# ProDocument_frontend_2024-01-22.net
KiCad netlist of a schematic drawn in EasyEDA Pro
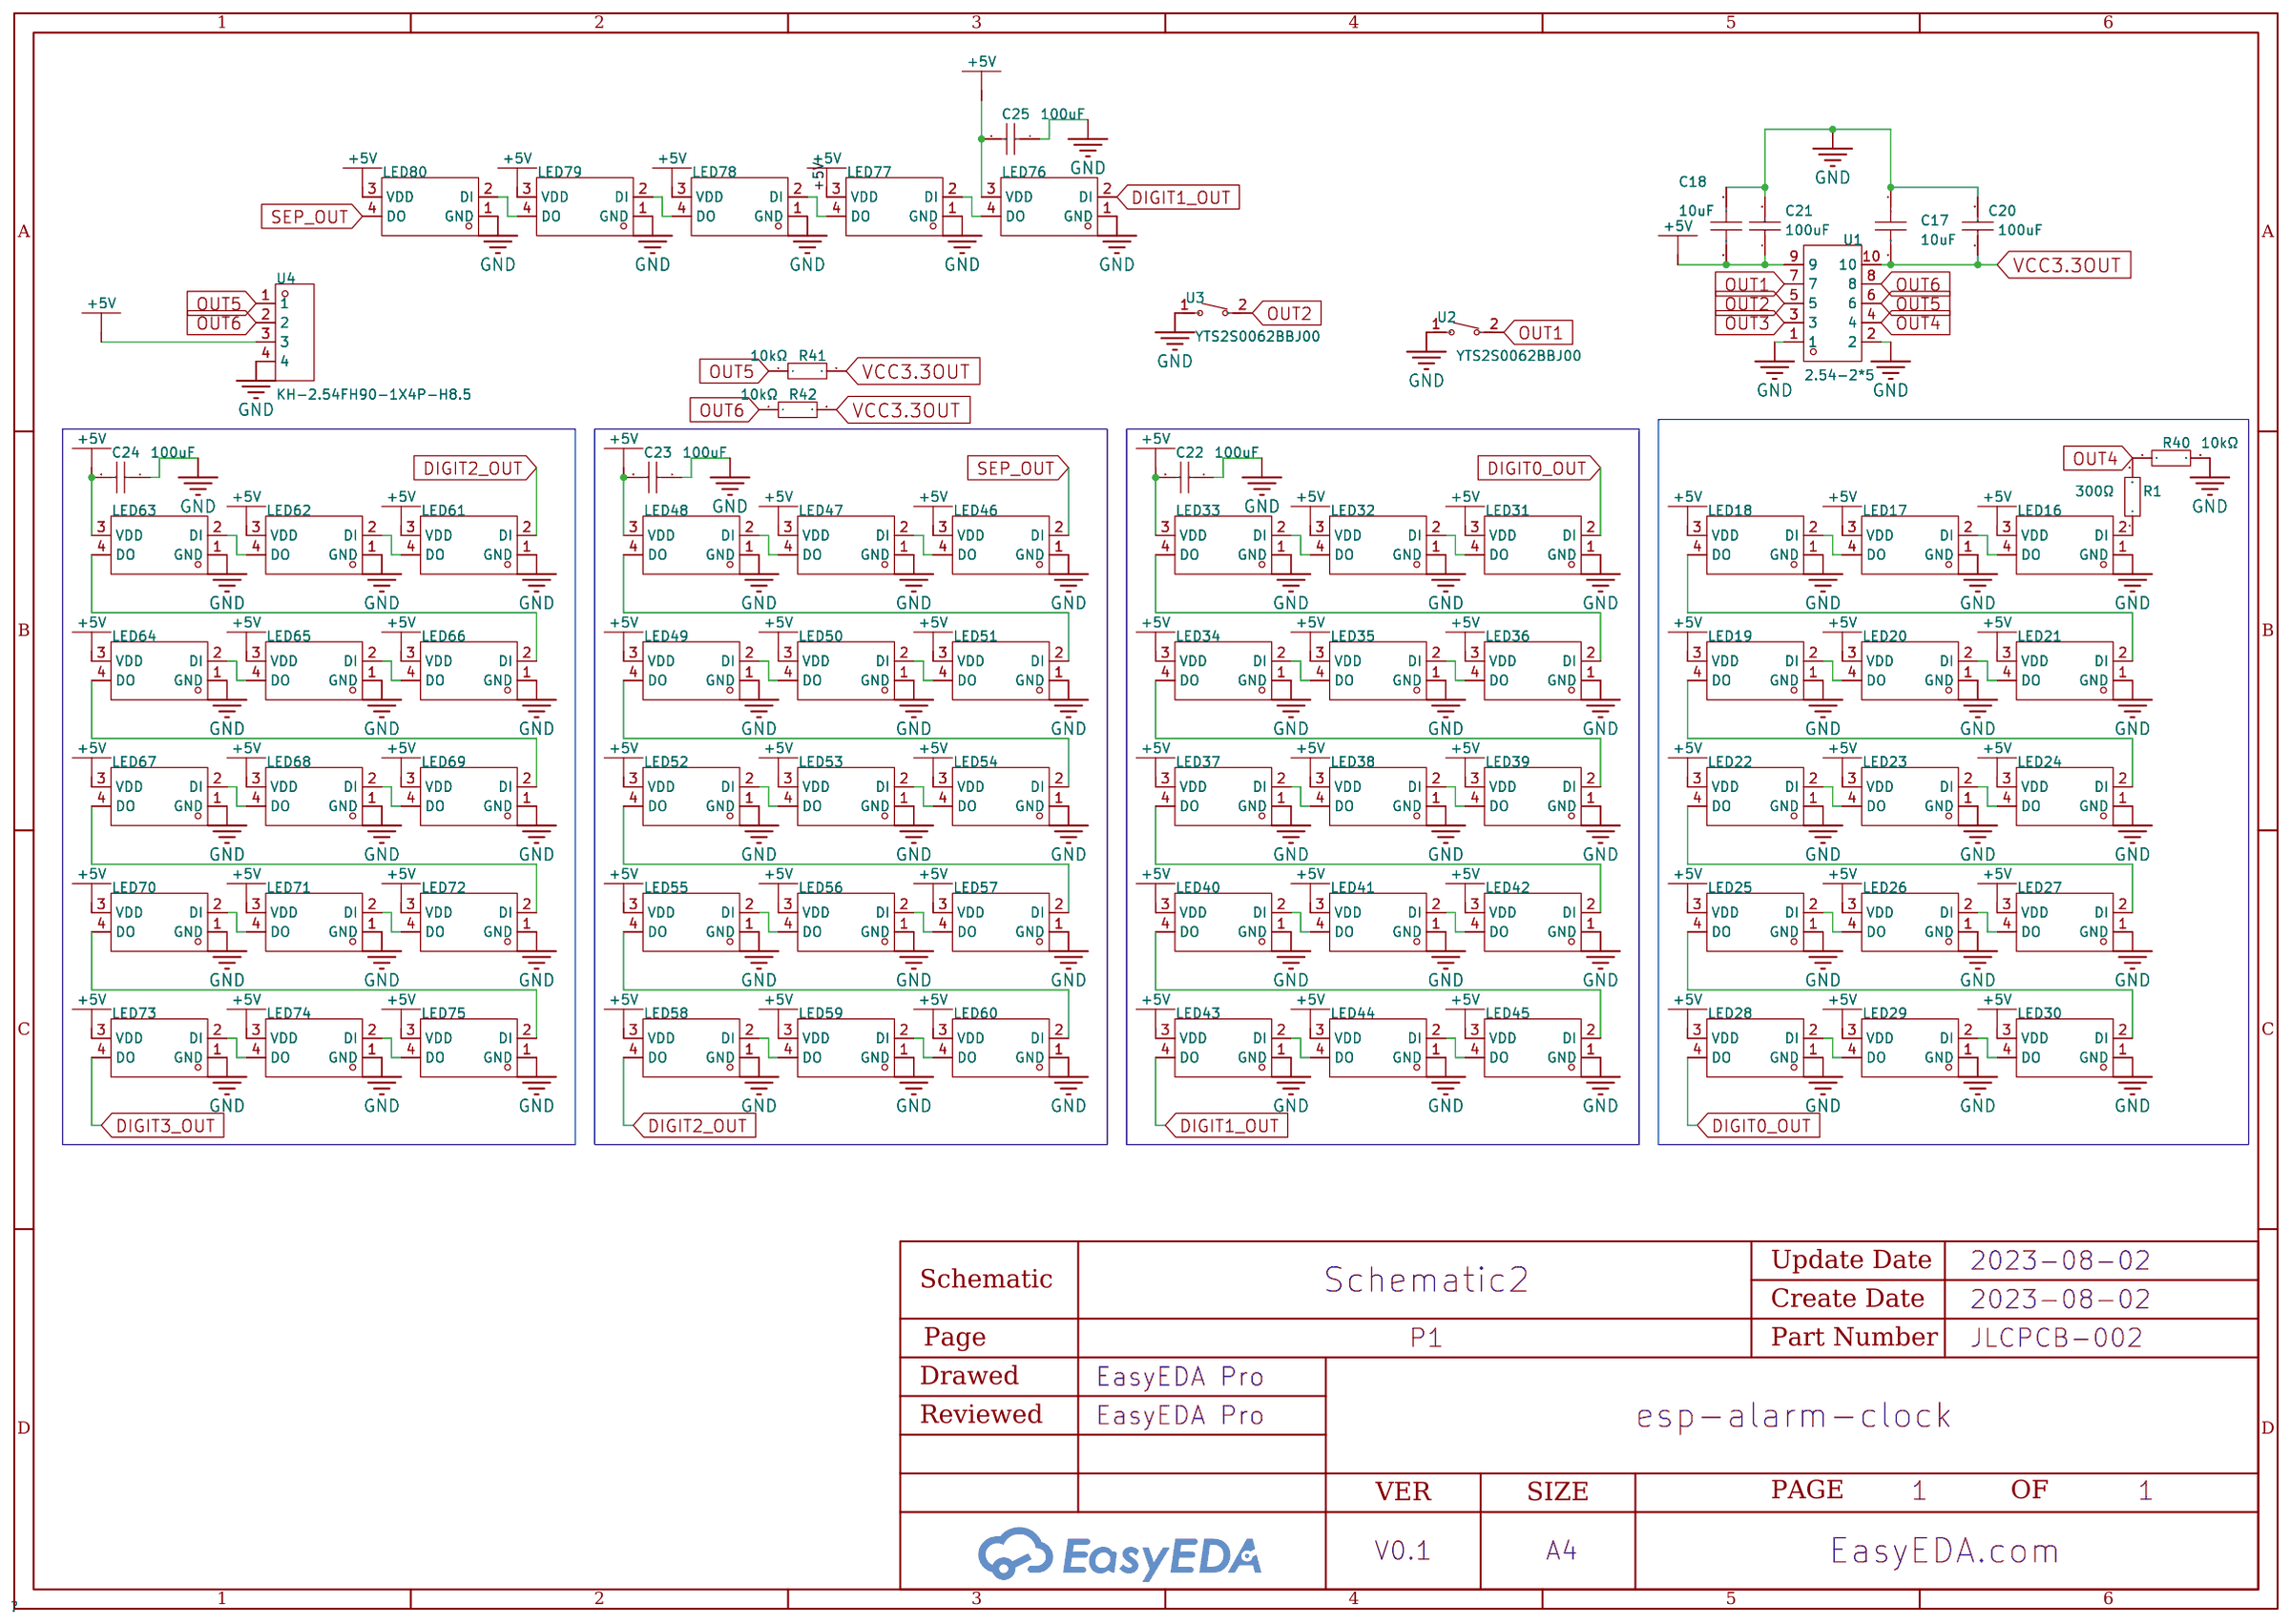
[diagram p0: schematic sheet]

(export (version "E")
  (design (tool "Eeschema 10.0.6"))
  (components
    (comp (ref "C17")
      (value "10uF")
      (footprint "easyedapro:C0603")
      (fields
        (field (name "Manufacturer Part") "TCC0603X5R106M6R3CT")
        (field (name "Manufacturer") "CCTC(三环)")
      )
      (libsource (lib "easyedapro") (part "TCC0603X5R106M6R3CT"))
    )
    (comp (ref "C18")
      (value "10uF")
      (footprint "easyedapro:C0603")
      (fields
        (field (name "Manufacturer Part") "TCC0603X5R106M6R3CT")
        (field (name "Manufacturer") "CCTC(三环)")
      )
      (libsource (lib "easyedapro") (part "TCC0603X5R106M6R3CT"))
    )
    (comp (ref "C20")
      (value "100uF")
      (footprint "easyedapro:C1206")
      (fields
        (field (name "Manufacturer Part") "CL31A107MQHNNNE")
        (field (name "Manufacturer") "SAMSUNG(三星)")
      )
      (libsource (lib "easyedapro") (part "CL31A107MQHNNNE"))
    )
    (comp (ref "C21")
      (value "100uF")
      (footprint "easyedapro:C1206")
      (fields
        (field (name "Manufacturer Part") "CL31A107MQHNNNE")
        (field (name "Manufacturer") "SAMSUNG(三星)")
      )
      (libsource (lib "easyedapro") (part "CL31A107MQHNNNE"))
    )
    (comp (ref "C22")
      (value "100uF")
      (footprint "easyedapro:C1206")
      (fields
        (field (name "Manufacturer Part") "CL31A107MQHNNNE")
        (field (name "Manufacturer") "SAMSUNG(三星)")
      )
      (libsource (lib "easyedapro") (part "CL31A107MQHNNNE"))
    )
    (comp (ref "C23")
      (value "100uF")
      (footprint "easyedapro:C1206")
      (fields
        (field (name "Manufacturer Part") "CL31A107MQHNNNE")
        (field (name "Manufacturer") "SAMSUNG(三星)")
      )
      (libsource (lib "easyedapro") (part "CL31A107MQHNNNE"))
    )
    (comp (ref "C24")
      (value "100uF")
      (footprint "easyedapro:C1206")
      (fields
        (field (name "Manufacturer Part") "CL31A107MQHNNNE")
        (field (name "Manufacturer") "SAMSUNG(三星)")
      )
      (libsource (lib "easyedapro") (part "CL31A107MQHNNNE"))
    )
    (comp (ref "C25")
      (value "100uF")
      (footprint "easyedapro:C1206")
      (fields
        (field (name "Manufacturer Part") "CL31A107MQHNNNE")
        (field (name "Manufacturer") "SAMSUNG(三星)")
      )
      (libsource (lib "easyedapro") (part "CL31A107MQHNNNE"))
    )
    (comp (ref "LED16")
      (value "XL-3528RGBW-WS2812B")
      (footprint "easyedapro:LED-SMD_4P-L3.5-W2.8-BR-1")
      (fields (field (name "Manufacturer") "XINGLIGHT(成兴光)"))
      (libsource (lib "easyedapro") (part "XL-3528RGBW-WS2812B"))
    )
    (comp (ref "LED17")
      (value "XL-3528RGBW-WS2812B")
      (footprint "easyedapro:LED-SMD_4P-L3.5-W2.8-BR-1")
      (fields (field (name "Manufacturer") "XINGLIGHT(成兴光)"))
      (libsource (lib "easyedapro") (part "XL-3528RGBW-WS2812B"))
    )
    (comp (ref "LED18")
      (value "XL-3528RGBW-WS2812B")
      (footprint "easyedapro:LED-SMD_4P-L3.5-W2.8-BR-1")
      (fields (field (name "Manufacturer") "XINGLIGHT(成兴光)"))
      (libsource (lib "easyedapro") (part "XL-3528RGBW-WS2812B"))
    )
    (comp (ref "LED19")
      (value "XL-3528RGBW-WS2812B")
      (footprint "easyedapro:LED-SMD_4P-L3.5-W2.8-BR-1")
      (fields (field (name "Manufacturer") "XINGLIGHT(成兴光)"))
      (libsource (lib "easyedapro") (part "XL-3528RGBW-WS2812B"))
    )
    (comp (ref "LED20")
      (value "XL-3528RGBW-WS2812B")
      (footprint "easyedapro:LED-SMD_4P-L3.5-W2.8-BR-1")
      (fields (field (name "Manufacturer") "XINGLIGHT(成兴光)"))
      (libsource (lib "easyedapro") (part "XL-3528RGBW-WS2812B"))
    )
    (comp (ref "LED21")
      (value "XL-3528RGBW-WS2812B")
      (footprint "easyedapro:LED-SMD_4P-L3.5-W2.8-BR-1")
      (fields (field (name "Manufacturer") "XINGLIGHT(成兴光)"))
      (libsource (lib "easyedapro") (part "XL-3528RGBW-WS2812B"))
    )
    (comp (ref "LED22")
      (value "XL-3528RGBW-WS2812B")
      (footprint "easyedapro:LED-SMD_4P-L3.5-W2.8-BR-1")
      (fields (field (name "Manufacturer") "XINGLIGHT(成兴光)"))
      (libsource (lib "easyedapro") (part "XL-3528RGBW-WS2812B"))
    )
    (comp (ref "LED23")
      (value "XL-3528RGBW-WS2812B")
      (footprint "easyedapro:LED-SMD_4P-L3.5-W2.8-BR-1")
      (fields (field (name "Manufacturer") "XINGLIGHT(成兴光)"))
      (libsource (lib "easyedapro") (part "XL-3528RGBW-WS2812B"))
    )
    (comp (ref "LED24")
      (value "XL-3528RGBW-WS2812B")
      (footprint "easyedapro:LED-SMD_4P-L3.5-W2.8-BR-1")
      (fields (field (name "Manufacturer") "XINGLIGHT(成兴光)"))
      (libsource (lib "easyedapro") (part "XL-3528RGBW-WS2812B"))
    )
    (comp (ref "LED25")
      (value "XL-3528RGBW-WS2812B")
      (footprint "easyedapro:LED-SMD_4P-L3.5-W2.8-BR-1")
      (fields (field (name "Manufacturer") "XINGLIGHT(成兴光)"))
      (libsource (lib "easyedapro") (part "XL-3528RGBW-WS2812B"))
    )
    (comp (ref "LED26")
      (value "XL-3528RGBW-WS2812B")
      (footprint "easyedapro:LED-SMD_4P-L3.5-W2.8-BR-1")
      (fields (field (name "Manufacturer") "XINGLIGHT(成兴光)"))
      (libsource (lib "easyedapro") (part "XL-3528RGBW-WS2812B"))
    )
    (comp (ref "LED27")
      (value "XL-3528RGBW-WS2812B")
      (footprint "easyedapro:LED-SMD_4P-L3.5-W2.8-BR-1")
      (fields (field (name "Manufacturer") "XINGLIGHT(成兴光)"))
      (libsource (lib "easyedapro") (part "XL-3528RGBW-WS2812B"))
    )
    (comp (ref "LED28")
      (value "XL-3528RGBW-WS2812B")
      (footprint "easyedapro:LED-SMD_4P-L3.5-W2.8-BR-1")
      (fields (field (name "Manufacturer") "XINGLIGHT(成兴光)"))
      (libsource (lib "easyedapro") (part "XL-3528RGBW-WS2812B"))
    )
    (comp (ref "LED29")
      (value "XL-3528RGBW-WS2812B")
      (footprint "easyedapro:LED-SMD_4P-L3.5-W2.8-BR-1")
      (fields (field (name "Manufacturer") "XINGLIGHT(成兴光)"))
      (libsource (lib "easyedapro") (part "XL-3528RGBW-WS2812B"))
    )
    (comp (ref "LED30")
      (value "XL-3528RGBW-WS2812B")
      (footprint "easyedapro:LED-SMD_4P-L3.5-W2.8-BR-1")
      (fields (field (name "Manufacturer") "XINGLIGHT(成兴光)"))
      (libsource (lib "easyedapro") (part "XL-3528RGBW-WS2812B"))
    )
    (comp (ref "LED31")
      (value "XL-3528RGBW-WS2812B")
      (footprint "easyedapro:LED-SMD_4P-L3.5-W2.8-BR-1")
      (fields (field (name "Manufacturer") "XINGLIGHT(成兴光)"))
      (libsource (lib "easyedapro") (part "XL-3528RGBW-WS2812B"))
    )
    (comp (ref "LED32")
      (value "XL-3528RGBW-WS2812B")
      (footprint "easyedapro:LED-SMD_4P-L3.5-W2.8-BR-1")
      (fields (field (name "Manufacturer") "XINGLIGHT(成兴光)"))
      (libsource (lib "easyedapro") (part "XL-3528RGBW-WS2812B"))
    )
    (comp (ref "LED33")
      (value "XL-3528RGBW-WS2812B")
      (footprint "easyedapro:LED-SMD_4P-L3.5-W2.8-BR-1")
      (fields (field (name "Manufacturer") "XINGLIGHT(成兴光)"))
      (libsource (lib "easyedapro") (part "XL-3528RGBW-WS2812B"))
    )
    (comp (ref "LED34")
      (value "XL-3528RGBW-WS2812B")
      (footprint "easyedapro:LED-SMD_4P-L3.5-W2.8-BR-1")
      (fields (field (name "Manufacturer") "XINGLIGHT(成兴光)"))
      (libsource (lib "easyedapro") (part "XL-3528RGBW-WS2812B"))
    )
    (comp (ref "LED35")
      (value "XL-3528RGBW-WS2812B")
      (footprint "easyedapro:LED-SMD_4P-L3.5-W2.8-BR-1")
      (fields (field (name "Manufacturer") "XINGLIGHT(成兴光)"))
      (libsource (lib "easyedapro") (part "XL-3528RGBW-WS2812B"))
    )
    (comp (ref "LED36")
      (value "XL-3528RGBW-WS2812B")
      (footprint "easyedapro:LED-SMD_4P-L3.5-W2.8-BR-1")
      (fields (field (name "Manufacturer") "XINGLIGHT(成兴光)"))
      (libsource (lib "easyedapro") (part "XL-3528RGBW-WS2812B"))
    )
    (comp (ref "LED37")
      (value "XL-3528RGBW-WS2812B")
      (footprint "easyedapro:LED-SMD_4P-L3.5-W2.8-BR-1")
      (fields (field (name "Manufacturer") "XINGLIGHT(成兴光)"))
      (libsource (lib "easyedapro") (part "XL-3528RGBW-WS2812B"))
    )
    (comp (ref "LED38")
      (value "XL-3528RGBW-WS2812B")
      (footprint "easyedapro:LED-SMD_4P-L3.5-W2.8-BR-1")
      (fields (field (name "Manufacturer") "XINGLIGHT(成兴光)"))
      (libsource (lib "easyedapro") (part "XL-3528RGBW-WS2812B"))
    )
    (comp (ref "LED39")
      (value "XL-3528RGBW-WS2812B")
      (footprint "easyedapro:LED-SMD_4P-L3.5-W2.8-BR-1")
      (fields (field (name "Manufacturer") "XINGLIGHT(成兴光)"))
      (libsource (lib "easyedapro") (part "XL-3528RGBW-WS2812B"))
    )
    (comp (ref "LED40")
      (value "XL-3528RGBW-WS2812B")
      (footprint "easyedapro:LED-SMD_4P-L3.5-W2.8-BR-1")
      (fields (field (name "Manufacturer") "XINGLIGHT(成兴光)"))
      (libsource (lib "easyedapro") (part "XL-3528RGBW-WS2812B"))
    )
    (comp (ref "LED41")
      (value "XL-3528RGBW-WS2812B")
      (footprint "easyedapro:LED-SMD_4P-L3.5-W2.8-BR-1")
      (fields (field (name "Manufacturer") "XINGLIGHT(成兴光)"))
      (libsource (lib "easyedapro") (part "XL-3528RGBW-WS2812B"))
    )
    (comp (ref "LED42")
      (value "XL-3528RGBW-WS2812B")
      (footprint "easyedapro:LED-SMD_4P-L3.5-W2.8-BR-1")
      (fields (field (name "Manufacturer") "XINGLIGHT(成兴光)"))
      (libsource (lib "easyedapro") (part "XL-3528RGBW-WS2812B"))
    )
    (comp (ref "LED43")
      (value "XL-3528RGBW-WS2812B")
      (footprint "easyedapro:LED-SMD_4P-L3.5-W2.8-BR-1")
      (fields (field (name "Manufacturer") "XINGLIGHT(成兴光)"))
      (libsource (lib "easyedapro") (part "XL-3528RGBW-WS2812B"))
    )
    (comp (ref "LED44")
      (value "XL-3528RGBW-WS2812B")
      (footprint "easyedapro:LED-SMD_4P-L3.5-W2.8-BR-1")
      (fields (field (name "Manufacturer") "XINGLIGHT(成兴光)"))
      (libsource (lib "easyedapro") (part "XL-3528RGBW-WS2812B"))
    )
    (comp (ref "LED45")
      (value "XL-3528RGBW-WS2812B")
      (footprint "easyedapro:LED-SMD_4P-L3.5-W2.8-BR-1")
      (fields (field (name "Manufacturer") "XINGLIGHT(成兴光)"))
      (libsource (lib "easyedapro") (part "XL-3528RGBW-WS2812B"))
    )
    (comp (ref "LED46")
      (value "XL-3528RGBW-WS2812B")
      (footprint "easyedapro:LED-SMD_4P-L3.5-W2.8-BR-1")
      (fields (field (name "Manufacturer") "XINGLIGHT(成兴光)"))
      (libsource (lib "easyedapro") (part "XL-3528RGBW-WS2812B"))
    )
    (comp (ref "LED47")
      (value "XL-3528RGBW-WS2812B")
      (footprint "easyedapro:LED-SMD_4P-L3.5-W2.8-BR-1")
      (fields (field (name "Manufacturer") "XINGLIGHT(成兴光)"))
      (libsource (lib "easyedapro") (part "XL-3528RGBW-WS2812B"))
    )
    (comp (ref "LED48")
      (value "XL-3528RGBW-WS2812B")
      (footprint "easyedapro:LED-SMD_4P-L3.5-W2.8-BR-1")
      (fields (field (name "Manufacturer") "XINGLIGHT(成兴光)"))
      (libsource (lib "easyedapro") (part "XL-3528RGBW-WS2812B"))
    )
    (comp (ref "LED49")
      (value "XL-3528RGBW-WS2812B")
      (footprint "easyedapro:LED-SMD_4P-L3.5-W2.8-BR-1")
      (fields (field (name "Manufacturer") "XINGLIGHT(成兴光)"))
      (libsource (lib "easyedapro") (part "XL-3528RGBW-WS2812B"))
    )
    (comp (ref "LED50")
      (value "XL-3528RGBW-WS2812B")
      (footprint "easyedapro:LED-SMD_4P-L3.5-W2.8-BR-1")
      (fields (field (name "Manufacturer") "XINGLIGHT(成兴光)"))
      (libsource (lib "easyedapro") (part "XL-3528RGBW-WS2812B"))
    )
    (comp (ref "LED51")
      (value "XL-3528RGBW-WS2812B")
      (footprint "easyedapro:LED-SMD_4P-L3.5-W2.8-BR-1")
      (fields (field (name "Manufacturer") "XINGLIGHT(成兴光)"))
      (libsource (lib "easyedapro") (part "XL-3528RGBW-WS2812B"))
    )
    (comp (ref "LED52")
      (value "XL-3528RGBW-WS2812B")
      (footprint "easyedapro:LED-SMD_4P-L3.5-W2.8-BR-1")
      (fields (field (name "Manufacturer") "XINGLIGHT(成兴光)"))
      (libsource (lib "easyedapro") (part "XL-3528RGBW-WS2812B"))
    )
    (comp (ref "LED53")
      (value "XL-3528RGBW-WS2812B")
      (footprint "easyedapro:LED-SMD_4P-L3.5-W2.8-BR-1")
      (fields (field (name "Manufacturer") "XINGLIGHT(成兴光)"))
      (libsource (lib "easyedapro") (part "XL-3528RGBW-WS2812B"))
    )
    (comp (ref "LED54")
      (value "XL-3528RGBW-WS2812B")
      (footprint "easyedapro:LED-SMD_4P-L3.5-W2.8-BR-1")
      (fields (field (name "Manufacturer") "XINGLIGHT(成兴光)"))
      (libsource (lib "easyedapro") (part "XL-3528RGBW-WS2812B"))
    )
    (comp (ref "LED55")
      (value "XL-3528RGBW-WS2812B")
      (footprint "easyedapro:LED-SMD_4P-L3.5-W2.8-BR-1")
      (fields (field (name "Manufacturer") "XINGLIGHT(成兴光)"))
      (libsource (lib "easyedapro") (part "XL-3528RGBW-WS2812B"))
    )
    (comp (ref "LED56")
      (value "XL-3528RGBW-WS2812B")
      (footprint "easyedapro:LED-SMD_4P-L3.5-W2.8-BR-1")
      (fields (field (name "Manufacturer") "XINGLIGHT(成兴光)"))
      (libsource (lib "easyedapro") (part "XL-3528RGBW-WS2812B"))
    )
    (comp (ref "LED57")
      (value "XL-3528RGBW-WS2812B")
      (footprint "easyedapro:LED-SMD_4P-L3.5-W2.8-BR-1")
      (fields (field (name "Manufacturer") "XINGLIGHT(成兴光)"))
      (libsource (lib "easyedapro") (part "XL-3528RGBW-WS2812B"))
    )
    (comp (ref "LED58")
      (value "XL-3528RGBW-WS2812B")
      (footprint "easyedapro:LED-SMD_4P-L3.5-W2.8-BR-1")
      (fields (field (name "Manufacturer") "XINGLIGHT(成兴光)"))
      (libsource (lib "easyedapro") (part "XL-3528RGBW-WS2812B"))
    )
    (comp (ref "LED59")
      (value "XL-3528RGBW-WS2812B")
      (footprint "easyedapro:LED-SMD_4P-L3.5-W2.8-BR-1")
      (fields (field (name "Manufacturer") "XINGLIGHT(成兴光)"))
      (libsource (lib "easyedapro") (part "XL-3528RGBW-WS2812B"))
    )
    (comp (ref "LED60")
      (value "XL-3528RGBW-WS2812B")
      (footprint "easyedapro:LED-SMD_4P-L3.5-W2.8-BR-1")
      (fields (field (name "Manufacturer") "XINGLIGHT(成兴光)"))
      (libsource (lib "easyedapro") (part "XL-3528RGBW-WS2812B"))
    )
    (comp (ref "LED61")
      (value "XL-3528RGBW-WS2812B")
      (footprint "easyedapro:LED-SMD_4P-L3.5-W2.8-BR-1")
      (fields (field (name "Manufacturer") "XINGLIGHT(成兴光)"))
      (libsource (lib "easyedapro") (part "XL-3528RGBW-WS2812B"))
    )
    (comp (ref "LED62")
      (value "XL-3528RGBW-WS2812B")
      (footprint "easyedapro:LED-SMD_4P-L3.5-W2.8-BR-1")
      (fields (field (name "Manufacturer") "XINGLIGHT(成兴光)"))
      (libsource (lib "easyedapro") (part "XL-3528RGBW-WS2812B"))
    )
    (comp (ref "LED63")
      (value "XL-3528RGBW-WS2812B")
      (footprint "easyedapro:LED-SMD_4P-L3.5-W2.8-BR-1")
      (fields (field (name "Manufacturer") "XINGLIGHT(成兴光)"))
      (libsource (lib "easyedapro") (part "XL-3528RGBW-WS2812B"))
    )
    (comp (ref "LED64")
      (value "XL-3528RGBW-WS2812B")
      (footprint "easyedapro:LED-SMD_4P-L3.5-W2.8-BR-1")
      (fields (field (name "Manufacturer") "XINGLIGHT(成兴光)"))
      (libsource (lib "easyedapro") (part "XL-3528RGBW-WS2812B"))
    )
    (comp (ref "LED65")
      (value "XL-3528RGBW-WS2812B")
      (footprint "easyedapro:LED-SMD_4P-L3.5-W2.8-BR-1")
      (fields (field (name "Manufacturer") "XINGLIGHT(成兴光)"))
      (libsource (lib "easyedapro") (part "XL-3528RGBW-WS2812B"))
    )
    (comp (ref "LED66")
      (value "XL-3528RGBW-WS2812B")
      (footprint "easyedapro:LED-SMD_4P-L3.5-W2.8-BR-1")
      (fields (field (name "Manufacturer") "XINGLIGHT(成兴光)"))
      (libsource (lib "easyedapro") (part "XL-3528RGBW-WS2812B"))
    )
    (comp (ref "LED67")
      (value "XL-3528RGBW-WS2812B")
      (footprint "easyedapro:LED-SMD_4P-L3.5-W2.8-BR-1")
      (fields (field (name "Manufacturer") "XINGLIGHT(成兴光)"))
      (libsource (lib "easyedapro") (part "XL-3528RGBW-WS2812B"))
    )
    (comp (ref "LED68")
      (value "XL-3528RGBW-WS2812B")
      (footprint "easyedapro:LED-SMD_4P-L3.5-W2.8-BR-1")
      (fields (field (name "Manufacturer") "XINGLIGHT(成兴光)"))
      (libsource (lib "easyedapro") (part "XL-3528RGBW-WS2812B"))
    )
    (comp (ref "LED69")
      (value "XL-3528RGBW-WS2812B")
      (footprint "easyedapro:LED-SMD_4P-L3.5-W2.8-BR-1")
      (fields (field (name "Manufacturer") "XINGLIGHT(成兴光)"))
      (libsource (lib "easyedapro") (part "XL-3528RGBW-WS2812B"))
    )
    (comp (ref "LED70")
      (value "XL-3528RGBW-WS2812B")
      (footprint "easyedapro:LED-SMD_4P-L3.5-W2.8-BR-1")
      (fields (field (name "Manufacturer") "XINGLIGHT(成兴光)"))
      (libsource (lib "easyedapro") (part "XL-3528RGBW-WS2812B"))
    )
    (comp (ref "LED71")
      (value "XL-3528RGBW-WS2812B")
      (footprint "easyedapro:LED-SMD_4P-L3.5-W2.8-BR-1")
      (fields (field (name "Manufacturer") "XINGLIGHT(成兴光)"))
      (libsource (lib "easyedapro") (part "XL-3528RGBW-WS2812B"))
    )
    (comp (ref "LED72")
      (value "XL-3528RGBW-WS2812B")
      (footprint "easyedapro:LED-SMD_4P-L3.5-W2.8-BR-1")
      (fields (field (name "Manufacturer") "XINGLIGHT(成兴光)"))
      (libsource (lib "easyedapro") (part "XL-3528RGBW-WS2812B"))
    )
    (comp (ref "LED73")
      (value "XL-3528RGBW-WS2812B")
      (footprint "easyedapro:LED-SMD_4P-L3.5-W2.8-BR-1")
      (fields (field (name "Manufacturer") "XINGLIGHT(成兴光)"))
      (libsource (lib "easyedapro") (part "XL-3528RGBW-WS2812B"))
    )
    (comp (ref "LED74")
      (value "XL-3528RGBW-WS2812B")
      (footprint "easyedapro:LED-SMD_4P-L3.5-W2.8-BR-1")
      (fields (field (name "Manufacturer") "XINGLIGHT(成兴光)"))
      (libsource (lib "easyedapro") (part "XL-3528RGBW-WS2812B"))
    )
    (comp (ref "LED75")
      (value "XL-3528RGBW-WS2812B")
      (footprint "easyedapro:LED-SMD_4P-L3.5-W2.8-BR-1")
      (fields (field (name "Manufacturer") "XINGLIGHT(成兴光)"))
      (libsource (lib "easyedapro") (part "XL-3528RGBW-WS2812B"))
    )
    (comp (ref "LED76")
      (value "XL-3528RGBW-WS2812B")
      (footprint "easyedapro:LED-SMD_4P-L3.5-W2.8-BR-1")
      (fields (field (name "Manufacturer") "XINGLIGHT(成兴光)"))
      (libsource (lib "easyedapro") (part "XL-3528RGBW-WS2812B"))
    )
    (comp (ref "LED77")
      (value "XL-3528RGBW-WS2812B")
      (footprint "easyedapro:LED-SMD_4P-L3.5-W2.8-BR-1")
      (fields (field (name "Manufacturer") "XINGLIGHT(成兴光)"))
      (libsource (lib "easyedapro") (part "XL-3528RGBW-WS2812B"))
    )
    (comp (ref "LED78")
      (value "XL-3528RGBW-WS2812B")
      (footprint "easyedapro:LED-SMD_4P-L3.5-W2.8-BR-1")
      (fields (field (name "Manufacturer") "XINGLIGHT(成兴光)"))
      (libsource (lib "easyedapro") (part "XL-3528RGBW-WS2812B"))
    )
    (comp (ref "LED79")
      (value "XL-3528RGBW-WS2812B")
      (footprint "easyedapro:LED-SMD_4P-L3.5-W2.8-BR-1")
      (fields (field (name "Manufacturer") "XINGLIGHT(成兴光)"))
      (libsource (lib "easyedapro") (part "XL-3528RGBW-WS2812B"))
    )
    (comp (ref "LED80")
      (value "XL-3528RGBW-WS2812B")
      (footprint "easyedapro:LED-SMD_4P-L3.5-W2.8-BR-1")
      (fields (field (name "Manufacturer") "XINGLIGHT(成兴光)"))
      (libsource (lib "easyedapro") (part "XL-3528RGBW-WS2812B"))
    )
    (comp (ref "R1")
      (value "300Ω")
      (footprint "easyedapro:R0603")
      (fields
        (field (name "Manufacturer Part") "0603WAF3000T5E")
        (field (name "Manufacturer") "UNI-ROYAL(厚声)")
      )
      (libsource (lib "easyedapro") (part "0603WAF3000T5E"))
    )
    (comp (ref "R40")
      (value "10kΩ")
      (footprint "easyedapro:R0603")
      (fields (field (name "Manufacturer Part") "RC0603FR-0710KL") (field (name "Manufacturer") "YAGEO(国巨)"))
      (libsource (lib "easyedapro") (part "RC0603FR-0710KL"))
    )
    (comp (ref "R41")
      (value "10kΩ")
      (footprint "easyedapro:R0603")
      (fields (field (name "Manufacturer Part") "RC0603FR-0710KL") (field (name "Manufacturer") "YAGEO(国巨)"))
      (libsource (lib "easyedapro") (part "RC0603FR-0710KL"))
    )
    (comp (ref "R42")
      (value "10kΩ")
      (footprint "easyedapro:R0603")
      (fields (field (name "Manufacturer Part") "RC0603FR-0710KL") (field (name "Manufacturer") "YAGEO(国巨)"))
      (libsource (lib "easyedapro") (part "RC0603FR-0710KL"))
    )
    (comp (ref "U1")
      (value "2.54-2*5")
      (footprint "easyedapro:HDR-TH_10P-P2.54-V-F-R2-C5-S2.54")
      (fields (field (name "Manufacturer") "ZHOURI(洲日)"))
      (libsource (lib "easyedapro") (part "2.54-2*5"))
    )
    (comp (ref "U2")
      (value "YTS2S0062BBJ00")
      (footprint "easyedapro:KEY-SMD_L6.0-W6.0-LS6.6")
      (description "Operating Force:200gf Switch Length:6mm Switch Width:6mm Switch Height:5mm")
      (fields (field (name "Manufacturer") "YIYUAN(怡远)"))
      (libsource (lib "easyedapro") (part "YTS2S0062BBJ00"))
    )
    (comp (ref "U3")
      (value "YTS2S0062BBJ00")
      (footprint "easyedapro:KEY-SMD_L6.0-W6.0-LS6.6")
      (description "Operating Force:200gf Switch Length:6mm Switch Width:6mm Switch Height:5mm")
      (fields (field (name "Manufacturer") "YIYUAN(怡远)"))
      (libsource (lib "easyedapro") (part "YTS2S0062BBJ00"))
    )
    (comp (ref "U4")
      (value "KH-2.54FH90-1X4P-H8.5")
      (footprint "easyedapro:HDR-TH_4P-P2.54-H-F-W10.2")
      (fields (field (name "Manufacturer") "kinghelm(金航标)"))
      (libsource (lib "easyedapro") (part "KH-2.54FH90-1X4P-H8.5"))
    )
  )
  (nets
    (net (code "1") (name "+5V") (class "Default")
      (node (ref "C18") (pin "2") (pinfunction "2_2") (pintype "input"))
      (node (ref "C21") (pin "1") (pinfunction "1_1") (pintype "input"))
      (node (ref "C22") (pin "2") (pinfunction "2_2") (pintype "input"))
      (node (ref "C23") (pin "2") (pinfunction "2_2") (pintype "input"))
      (node (ref "C24") (pin "2") (pinfunction "2_2") (pintype "input"))
      (node (ref "C25") (pin "2") (pinfunction "2_2") (pintype "input"))
      (node (ref "LED16") (pin "3") (pinfunction "VDD_3") (pintype "input"))
      (node (ref "LED17") (pin "3") (pinfunction "VDD_3") (pintype "input"))
      (node (ref "LED18") (pin "3") (pinfunction "VDD_3") (pintype "input"))
      (node (ref "LED19") (pin "3") (pinfunction "VDD_3") (pintype "input"))
      (node (ref "LED20") (pin "3") (pinfunction "VDD_3") (pintype "input"))
      (node (ref "LED21") (pin "3") (pinfunction "VDD_3") (pintype "input"))
      (node (ref "LED22") (pin "3") (pinfunction "VDD_3") (pintype "input"))
      (node (ref "LED23") (pin "3") (pinfunction "VDD_3") (pintype "input"))
      (node (ref "LED24") (pin "3") (pinfunction "VDD_3") (pintype "input"))
      (node (ref "LED25") (pin "3") (pinfunction "VDD_3") (pintype "input"))
      (node (ref "LED26") (pin "3") (pinfunction "VDD_3") (pintype "input"))
      (node (ref "LED27") (pin "3") (pinfunction "VDD_3") (pintype "input"))
      (node (ref "LED28") (pin "3") (pinfunction "VDD_3") (pintype "input"))
      (node (ref "LED29") (pin "3") (pinfunction "VDD_3") (pintype "input"))
      (node (ref "LED30") (pin "3") (pinfunction "VDD_3") (pintype "input"))
      (node (ref "LED31") (pin "3") (pinfunction "VDD_3") (pintype "input"))
      (node (ref "LED32") (pin "3") (pinfunction "VDD_3") (pintype "input"))
      (node (ref "LED33") (pin "3") (pinfunction "VDD_3") (pintype "input"))
      (node (ref "LED34") (pin "3") (pinfunction "VDD_3") (pintype "input"))
      (node (ref "LED35") (pin "3") (pinfunction "VDD_3") (pintype "input"))
      (node (ref "LED36") (pin "3") (pinfunction "VDD_3") (pintype "input"))
      (node (ref "LED37") (pin "3") (pinfunction "VDD_3") (pintype "input"))
      (node (ref "LED38") (pin "3") (pinfunction "VDD_3") (pintype "input"))
      (node (ref "LED39") (pin "3") (pinfunction "VDD_3") (pintype "input"))
      (node (ref "LED40") (pin "3") (pinfunction "VDD_3") (pintype "input"))
      (node (ref "LED41") (pin "3") (pinfunction "VDD_3") (pintype "input"))
      (node (ref "LED42") (pin "3") (pinfunction "VDD_3") (pintype "input"))
      (node (ref "LED43") (pin "3") (pinfunction "VDD_3") (pintype "input"))
      (node (ref "LED44") (pin "3") (pinfunction "VDD_3") (pintype "input"))
      (node (ref "LED45") (pin "3") (pinfunction "VDD_3") (pintype "input"))
      (node (ref "LED46") (pin "3") (pinfunction "VDD_3") (pintype "input"))
      (node (ref "LED47") (pin "3") (pinfunction "VDD_3") (pintype "input"))
      (node (ref "LED48") (pin "3") (pinfunction "VDD_3") (pintype "input"))
      (node (ref "LED49") (pin "3") (pinfunction "VDD_3") (pintype "input"))
      (node (ref "LED50") (pin "3") (pinfunction "VDD_3") (pintype "input"))
      (node (ref "LED51") (pin "3") (pinfunction "VDD_3") (pintype "input"))
      (node (ref "LED52") (pin "3") (pinfunction "VDD_3") (pintype "input"))
      (node (ref "LED53") (pin "3") (pinfunction "VDD_3") (pintype "input"))
      (node (ref "LED54") (pin "3") (pinfunction "VDD_3") (pintype "input"))
      (node (ref "LED55") (pin "3") (pinfunction "VDD_3") (pintype "input"))
      (node (ref "LED56") (pin "3") (pinfunction "VDD_3") (pintype "input"))
      (node (ref "LED57") (pin "3") (pinfunction "VDD_3") (pintype "input"))
      (node (ref "LED58") (pin "3") (pinfunction "VDD_3") (pintype "input"))
      (node (ref "LED59") (pin "3") (pinfunction "VDD_3") (pintype "input"))
      (node (ref "LED60") (pin "3") (pinfunction "VDD_3") (pintype "input"))
      (node (ref "LED61") (pin "3") (pinfunction "VDD_3") (pintype "input"))
      (node (ref "LED62") (pin "3") (pinfunction "VDD_3") (pintype "input"))
      (node (ref "LED63") (pin "3") (pinfunction "VDD_3") (pintype "input"))
      (node (ref "LED64") (pin "3") (pinfunction "VDD_3") (pintype "input"))
      (node (ref "LED65") (pin "3") (pinfunction "VDD_3") (pintype "input"))
      (node (ref "LED66") (pin "3") (pinfunction "VDD_3") (pintype "input"))
      (node (ref "LED67") (pin "3") (pinfunction "VDD_3") (pintype "input"))
      (node (ref "LED68") (pin "3") (pinfunction "VDD_3") (pintype "input"))
      (node (ref "LED69") (pin "3") (pinfunction "VDD_3") (pintype "input"))
      (node (ref "LED70") (pin "3") (pinfunction "VDD_3") (pintype "input"))
      (node (ref "LED71") (pin "3") (pinfunction "VDD_3") (pintype "input"))
      (node (ref "LED72") (pin "3") (pinfunction "VDD_3") (pintype "input"))
      (node (ref "LED73") (pin "3") (pinfunction "VDD_3") (pintype "input"))
      (node (ref "LED74") (pin "3") (pinfunction "VDD_3") (pintype "input"))
      (node (ref "LED75") (pin "3") (pinfunction "VDD_3") (pintype "input"))
      (node (ref "LED76") (pin "3") (pinfunction "VDD_3") (pintype "input"))
      (node (ref "LED77") (pin "3") (pinfunction "VDD_3") (pintype "input"))
      (node (ref "LED78") (pin "3") (pinfunction "VDD_3") (pintype "input"))
      (node (ref "LED79") (pin "3") (pinfunction "VDD_3") (pintype "input"))
      (node (ref "LED80") (pin "3") (pinfunction "VDD_3") (pintype "input"))
      (node (ref "U1") (pin "9") (pinfunction "9_9") (pintype "input"))
      (node (ref "U4") (pin "3") (pinfunction "3_3") (pintype "input"))
    )
    (net (code "2") (name "DIGIT0_OUT") (class "Default")
      (node (ref "LED28") (pin "4") (pinfunction "DO_4") (pintype "input"))
      (node (ref "LED31") (pin "2") (pinfunction "DI_2") (pintype "input"))
    )
    (net (code "3") (name "DIGIT1_OUT") (class "Default")
      (node (ref "LED43") (pin "4") (pinfunction "DO_4") (pintype "input"))
      (node (ref "LED76") (pin "2") (pinfunction "DI_2") (pintype "input"))
    )
    (net (code "4") (name "DIGIT2_OUT") (class "Default")
      (node (ref "LED58") (pin "4") (pinfunction "DO_4") (pintype "input"))
      (node (ref "LED61") (pin "2") (pinfunction "DI_2") (pintype "input"))
    )
    (net (code "5") (name "DIGIT3_OUT") (class "Default")
      (node (ref "LED73") (pin "4") (pinfunction "DO_4") (pintype "input"))
    )
    (net (code "6") (name "GND") (class "Default")
      (node (ref "C17") (pin "1") (pinfunction "1_1") (pintype "input"))
      (node (ref "C18") (pin "1") (pinfunction "1_1") (pintype "input"))
      (node (ref "C20") (pin "2") (pinfunction "2_2") (pintype "input"))
      (node (ref "C21") (pin "2") (pinfunction "2_2") (pintype "input"))
      (node (ref "C22") (pin "1") (pinfunction "1_1") (pintype "input"))
      (node (ref "C23") (pin "1") (pinfunction "1_1") (pintype "input"))
      (node (ref "C24") (pin "1") (pinfunction "1_1") (pintype "input"))
      (node (ref "C25") (pin "1") (pinfunction "1_1") (pintype "input"))
      (node (ref "LED16") (pin "1") (pinfunction "GND_1") (pintype "input"))
      (node (ref "LED17") (pin "1") (pinfunction "GND_1") (pintype "input"))
      (node (ref "LED18") (pin "1") (pinfunction "GND_1") (pintype "input"))
      (node (ref "LED19") (pin "1") (pinfunction "GND_1") (pintype "input"))
      (node (ref "LED20") (pin "1") (pinfunction "GND_1") (pintype "input"))
      (node (ref "LED21") (pin "1") (pinfunction "GND_1") (pintype "input"))
      (node (ref "LED22") (pin "1") (pinfunction "GND_1") (pintype "input"))
      (node (ref "LED23") (pin "1") (pinfunction "GND_1") (pintype "input"))
      (node (ref "LED24") (pin "1") (pinfunction "GND_1") (pintype "input"))
      (node (ref "LED25") (pin "1") (pinfunction "GND_1") (pintype "input"))
      (node (ref "LED26") (pin "1") (pinfunction "GND_1") (pintype "input"))
      (node (ref "LED27") (pin "1") (pinfunction "GND_1") (pintype "input"))
      (node (ref "LED28") (pin "1") (pinfunction "GND_1") (pintype "input"))
      (node (ref "LED29") (pin "1") (pinfunction "GND_1") (pintype "input"))
      (node (ref "LED30") (pin "1") (pinfunction "GND_1") (pintype "input"))
      (node (ref "LED31") (pin "1") (pinfunction "GND_1") (pintype "input"))
      (node (ref "LED32") (pin "1") (pinfunction "GND_1") (pintype "input"))
      (node (ref "LED33") (pin "1") (pinfunction "GND_1") (pintype "input"))
      (node (ref "LED34") (pin "1") (pinfunction "GND_1") (pintype "input"))
      (node (ref "LED35") (pin "1") (pinfunction "GND_1") (pintype "input"))
      (node (ref "LED36") (pin "1") (pinfunction "GND_1") (pintype "input"))
      (node (ref "LED37") (pin "1") (pinfunction "GND_1") (pintype "input"))
      (node (ref "LED38") (pin "1") (pinfunction "GND_1") (pintype "input"))
      (node (ref "LED39") (pin "1") (pinfunction "GND_1") (pintype "input"))
      (node (ref "LED40") (pin "1") (pinfunction "GND_1") (pintype "input"))
      (node (ref "LED41") (pin "1") (pinfunction "GND_1") (pintype "input"))
      (node (ref "LED42") (pin "1") (pinfunction "GND_1") (pintype "input"))
      (node (ref "LED43") (pin "1") (pinfunction "GND_1") (pintype "input"))
      (node (ref "LED44") (pin "1") (pinfunction "GND_1") (pintype "input"))
      (node (ref "LED45") (pin "1") (pinfunction "GND_1") (pintype "input"))
      (node (ref "LED46") (pin "1") (pinfunction "GND_1") (pintype "input"))
      (node (ref "LED47") (pin "1") (pinfunction "GND_1") (pintype "input"))
      (node (ref "LED48") (pin "1") (pinfunction "GND_1") (pintype "input"))
      (node (ref "LED49") (pin "1") (pinfunction "GND_1") (pintype "input"))
      (node (ref "LED50") (pin "1") (pinfunction "GND_1") (pintype "input"))
      (node (ref "LED51") (pin "1") (pinfunction "GND_1") (pintype "input"))
      (node (ref "LED52") (pin "1") (pinfunction "GND_1") (pintype "input"))
      (node (ref "LED53") (pin "1") (pinfunction "GND_1") (pintype "input"))
      (node (ref "LED54") (pin "1") (pinfunction "GND_1") (pintype "input"))
      (node (ref "LED55") (pin "1") (pinfunction "GND_1") (pintype "input"))
      (node (ref "LED56") (pin "1") (pinfunction "GND_1") (pintype "input"))
      (node (ref "LED57") (pin "1") (pinfunction "GND_1") (pintype "input"))
      (node (ref "LED58") (pin "1") (pinfunction "GND_1") (pintype "input"))
      (node (ref "LED59") (pin "1") (pinfunction "GND_1") (pintype "input"))
      (node (ref "LED60") (pin "1") (pinfunction "GND_1") (pintype "input"))
      (node (ref "LED61") (pin "1") (pinfunction "GND_1") (pintype "input"))
      (node (ref "LED62") (pin "1") (pinfunction "GND_1") (pintype "input"))
      (node (ref "LED63") (pin "1") (pinfunction "GND_1") (pintype "input"))
      (node (ref "LED64") (pin "1") (pinfunction "GND_1") (pintype "input"))
      (node (ref "LED65") (pin "1") (pinfunction "GND_1") (pintype "input"))
      (node (ref "LED66") (pin "1") (pinfunction "GND_1") (pintype "input"))
      (node (ref "LED67") (pin "1") (pinfunction "GND_1") (pintype "input"))
      (node (ref "LED68") (pin "1") (pinfunction "GND_1") (pintype "input"))
      (node (ref "LED69") (pin "1") (pinfunction "GND_1") (pintype "input"))
      (node (ref "LED70") (pin "1") (pinfunction "GND_1") (pintype "input"))
      (node (ref "LED71") (pin "1") (pinfunction "GND_1") (pintype "input"))
      (node (ref "LED72") (pin "1") (pinfunction "GND_1") (pintype "input"))
      (node (ref "LED73") (pin "1") (pinfunction "GND_1") (pintype "input"))
      (node (ref "LED74") (pin "1") (pinfunction "GND_1") (pintype "input"))
      (node (ref "LED75") (pin "1") (pinfunction "GND_1") (pintype "input"))
      (node (ref "LED76") (pin "1") (pinfunction "GND_1") (pintype "input"))
      (node (ref "LED77") (pin "1") (pinfunction "GND_1") (pintype "input"))
      (node (ref "LED78") (pin "1") (pinfunction "GND_1") (pintype "input"))
      (node (ref "LED79") (pin "1") (pinfunction "GND_1") (pintype "input"))
      (node (ref "LED80") (pin "1") (pinfunction "GND_1") (pintype "input"))
      (node (ref "R40") (pin "2") (pinfunction "2_2") (pintype "input"))
      (node (ref "U1") (pin "1") (pinfunction "1_1") (pintype "input"))
      (node (ref "U1") (pin "2") (pinfunction "2_2") (pintype "input"))
      (node (ref "U2") (pin "1") (pinfunction "A_1") (pintype "input"))
      (node (ref "U3") (pin "1") (pinfunction "A_1") (pintype "input"))
      (node (ref "U4") (pin "4") (pinfunction "4_4") (pintype "input"))
    )
    (net (code "7") (name "Net-(LED16-DI)") (class "Default")
      (node (ref "LED16") (pin "2") (pinfunction "DI_2") (pintype "input"))
      (node (ref "R1") (pin "1") (pinfunction "1_1") (pintype "input"))
    )
    (net (code "8") (name "Net-(LED16-DO)") (class "Default")
      (node (ref "LED16") (pin "4") (pinfunction "DO_4") (pintype "input"))
      (node (ref "LED17") (pin "2") (pinfunction "DI_2") (pintype "input"))
    )
    (net (code "9") (name "Net-(LED17-DO)") (class "Default")
      (node (ref "LED17") (pin "4") (pinfunction "DO_4") (pintype "input"))
      (node (ref "LED18") (pin "2") (pinfunction "DI_2") (pintype "input"))
    )
    (net (code "10") (name "Net-(LED18-DO)") (class "Default")
      (node (ref "LED18") (pin "4") (pinfunction "DO_4") (pintype "input"))
      (node (ref "LED21") (pin "2") (pinfunction "DI_2") (pintype "input"))
    )
    (net (code "11") (name "Net-(LED19-DI)") (class "Default")
      (node (ref "LED19") (pin "2") (pinfunction "DI_2") (pintype "input"))
      (node (ref "LED20") (pin "4") (pinfunction "DO_4") (pintype "input"))
    )
    (net (code "12") (name "Net-(LED19-DO)") (class "Default")
      (node (ref "LED19") (pin "4") (pinfunction "DO_4") (pintype "input"))
      (node (ref "LED24") (pin "2") (pinfunction "DI_2") (pintype "input"))
    )
    (net (code "13") (name "Net-(LED20-DI)") (class "Default")
      (node (ref "LED20") (pin "2") (pinfunction "DI_2") (pintype "input"))
      (node (ref "LED21") (pin "4") (pinfunction "DO_4") (pintype "input"))
    )
    (net (code "14") (name "Net-(LED22-DI)") (class "Default")
      (node (ref "LED22") (pin "2") (pinfunction "DI_2") (pintype "input"))
      (node (ref "LED23") (pin "4") (pinfunction "DO_4") (pintype "input"))
    )
    (net (code "15") (name "Net-(LED22-DO)") (class "Default")
      (node (ref "LED22") (pin "4") (pinfunction "DO_4") (pintype "input"))
      (node (ref "LED27") (pin "2") (pinfunction "DI_2") (pintype "input"))
    )
    (net (code "16") (name "Net-(LED23-DI)") (class "Default")
      (node (ref "LED23") (pin "2") (pinfunction "DI_2") (pintype "input"))
      (node (ref "LED24") (pin "4") (pinfunction "DO_4") (pintype "input"))
    )
    (net (code "17") (name "Net-(LED25-DI)") (class "Default")
      (node (ref "LED25") (pin "2") (pinfunction "DI_2") (pintype "input"))
      (node (ref "LED26") (pin "4") (pinfunction "DO_4") (pintype "input"))
    )
    (net (code "18") (name "Net-(LED25-DO)") (class "Default")
      (node (ref "LED25") (pin "4") (pinfunction "DO_4") (pintype "input"))
      (node (ref "LED30") (pin "2") (pinfunction "DI_2") (pintype "input"))
    )
    (net (code "19") (name "Net-(LED26-DI)") (class "Default")
      (node (ref "LED26") (pin "2") (pinfunction "DI_2") (pintype "input"))
      (node (ref "LED27") (pin "4") (pinfunction "DO_4") (pintype "input"))
    )
    (net (code "20") (name "Net-(LED28-DI)") (class "Default")
      (node (ref "LED28") (pin "2") (pinfunction "DI_2") (pintype "input"))
      (node (ref "LED29") (pin "4") (pinfunction "DO_4") (pintype "input"))
    )
    (net (code "21") (name "Net-(LED29-DI)") (class "Default")
      (node (ref "LED29") (pin "2") (pinfunction "DI_2") (pintype "input"))
      (node (ref "LED30") (pin "4") (pinfunction "DO_4") (pintype "input"))
    )
    (net (code "22") (name "Net-(LED31-DO)") (class "Default")
      (node (ref "LED31") (pin "4") (pinfunction "DO_4") (pintype "input"))
      (node (ref "LED32") (pin "2") (pinfunction "DI_2") (pintype "input"))
    )
    (net (code "23") (name "Net-(LED32-DO)") (class "Default")
      (node (ref "LED32") (pin "4") (pinfunction "DO_4") (pintype "input"))
      (node (ref "LED33") (pin "2") (pinfunction "DI_2") (pintype "input"))
    )
    (net (code "24") (name "Net-(LED33-DO)") (class "Default")
      (node (ref "LED33") (pin "4") (pinfunction "DO_4") (pintype "input"))
      (node (ref "LED36") (pin "2") (pinfunction "DI_2") (pintype "input"))
    )
    (net (code "25") (name "Net-(LED34-DI)") (class "Default")
      (node (ref "LED34") (pin "2") (pinfunction "DI_2") (pintype "input"))
      (node (ref "LED35") (pin "4") (pinfunction "DO_4") (pintype "input"))
    )
    (net (code "26") (name "Net-(LED34-DO)") (class "Default")
      (node (ref "LED34") (pin "4") (pinfunction "DO_4") (pintype "input"))
      (node (ref "LED39") (pin "2") (pinfunction "DI_2") (pintype "input"))
    )
    (net (code "27") (name "Net-(LED35-DI)") (class "Default")
      (node (ref "LED35") (pin "2") (pinfunction "DI_2") (pintype "input"))
      (node (ref "LED36") (pin "4") (pinfunction "DO_4") (pintype "input"))
    )
    (net (code "28") (name "Net-(LED37-DI)") (class "Default")
      (node (ref "LED37") (pin "2") (pinfunction "DI_2") (pintype "input"))
      (node (ref "LED38") (pin "4") (pinfunction "DO_4") (pintype "input"))
    )
    (net (code "29") (name "Net-(LED37-DO)") (class "Default")
      (node (ref "LED37") (pin "4") (pinfunction "DO_4") (pintype "input"))
      (node (ref "LED42") (pin "2") (pinfunction "DI_2") (pintype "input"))
    )
    (net (code "30") (name "Net-(LED38-DI)") (class "Default")
      (node (ref "LED38") (pin "2") (pinfunction "DI_2") (pintype "input"))
      (node (ref "LED39") (pin "4") (pinfunction "DO_4") (pintype "input"))
    )
    (net (code "31") (name "Net-(LED40-DI)") (class "Default")
      (node (ref "LED40") (pin "2") (pinfunction "DI_2") (pintype "input"))
      (node (ref "LED41") (pin "4") (pinfunction "DO_4") (pintype "input"))
    )
    (net (code "32") (name "Net-(LED40-DO)") (class "Default")
      (node (ref "LED40") (pin "4") (pinfunction "DO_4") (pintype "input"))
      (node (ref "LED45") (pin "2") (pinfunction "DI_2") (pintype "input"))
    )
    (net (code "33") (name "Net-(LED41-DI)") (class "Default")
      (node (ref "LED41") (pin "2") (pinfunction "DI_2") (pintype "input"))
      (node (ref "LED42") (pin "4") (pinfunction "DO_4") (pintype "input"))
    )
    (net (code "34") (name "Net-(LED43-DI)") (class "Default")
      (node (ref "LED43") (pin "2") (pinfunction "DI_2") (pintype "input"))
      (node (ref "LED44") (pin "4") (pinfunction "DO_4") (pintype "input"))
    )
    (net (code "35") (name "Net-(LED44-DI)") (class "Default")
      (node (ref "LED44") (pin "2") (pinfunction "DI_2") (pintype "input"))
      (node (ref "LED45") (pin "4") (pinfunction "DO_4") (pintype "input"))
    )
    (net (code "36") (name "Net-(LED46-DO)") (class "Default")
      (node (ref "LED46") (pin "4") (pinfunction "DO_4") (pintype "input"))
      (node (ref "LED47") (pin "2") (pinfunction "DI_2") (pintype "input"))
    )
    (net (code "37") (name "Net-(LED47-DO)") (class "Default")
      (node (ref "LED47") (pin "4") (pinfunction "DO_4") (pintype "input"))
      (node (ref "LED48") (pin "2") (pinfunction "DI_2") (pintype "input"))
    )
    (net (code "38") (name "Net-(LED48-DO)") (class "Default")
      (node (ref "LED48") (pin "4") (pinfunction "DO_4") (pintype "input"))
      (node (ref "LED51") (pin "2") (pinfunction "DI_2") (pintype "input"))
    )
    (net (code "39") (name "Net-(LED49-DI)") (class "Default")
      (node (ref "LED49") (pin "2") (pinfunction "DI_2") (pintype "input"))
      (node (ref "LED50") (pin "4") (pinfunction "DO_4") (pintype "input"))
    )
    (net (code "40") (name "Net-(LED49-DO)") (class "Default")
      (node (ref "LED49") (pin "4") (pinfunction "DO_4") (pintype "input"))
      (node (ref "LED54") (pin "2") (pinfunction "DI_2") (pintype "input"))
    )
    (net (code "41") (name "Net-(LED50-DI)") (class "Default")
      (node (ref "LED50") (pin "2") (pinfunction "DI_2") (pintype "input"))
      (node (ref "LED51") (pin "4") (pinfunction "DO_4") (pintype "input"))
    )
    (net (code "42") (name "Net-(LED52-DI)") (class "Default")
      (node (ref "LED52") (pin "2") (pinfunction "DI_2") (pintype "input"))
      (node (ref "LED53") (pin "4") (pinfunction "DO_4") (pintype "input"))
    )
    (net (code "43") (name "Net-(LED52-DO)") (class "Default")
      (node (ref "LED52") (pin "4") (pinfunction "DO_4") (pintype "input"))
      (node (ref "LED57") (pin "2") (pinfunction "DI_2") (pintype "input"))
    )
    (net (code "44") (name "Net-(LED53-DI)") (class "Default")
      (node (ref "LED53") (pin "2") (pinfunction "DI_2") (pintype "input"))
      (node (ref "LED54") (pin "4") (pinfunction "DO_4") (pintype "input"))
    )
    (net (code "45") (name "Net-(LED55-DI)") (class "Default")
      (node (ref "LED55") (pin "2") (pinfunction "DI_2") (pintype "input"))
      (node (ref "LED56") (pin "4") (pinfunction "DO_4") (pintype "input"))
    )
    (net (code "46") (name "Net-(LED55-DO)") (class "Default")
      (node (ref "LED55") (pin "4") (pinfunction "DO_4") (pintype "input"))
      (node (ref "LED60") (pin "2") (pinfunction "DI_2") (pintype "input"))
    )
    (net (code "47") (name "Net-(LED56-DI)") (class "Default")
      (node (ref "LED56") (pin "2") (pinfunction "DI_2") (pintype "input"))
      (node (ref "LED57") (pin "4") (pinfunction "DO_4") (pintype "input"))
    )
    (net (code "48") (name "Net-(LED58-DI)") (class "Default")
      (node (ref "LED58") (pin "2") (pinfunction "DI_2") (pintype "input"))
      (node (ref "LED59") (pin "4") (pinfunction "DO_4") (pintype "input"))
    )
    (net (code "49") (name "Net-(LED59-DI)") (class "Default")
      (node (ref "LED59") (pin "2") (pinfunction "DI_2") (pintype "input"))
      (node (ref "LED60") (pin "4") (pinfunction "DO_4") (pintype "input"))
    )
    (net (code "50") (name "Net-(LED61-DO)") (class "Default")
      (node (ref "LED61") (pin "4") (pinfunction "DO_4") (pintype "input"))
      (node (ref "LED62") (pin "2") (pinfunction "DI_2") (pintype "input"))
    )
    (net (code "51") (name "Net-(LED62-DO)") (class "Default")
      (node (ref "LED62") (pin "4") (pinfunction "DO_4") (pintype "input"))
      (node (ref "LED63") (pin "2") (pinfunction "DI_2") (pintype "input"))
    )
    (net (code "52") (name "Net-(LED63-DO)") (class "Default")
      (node (ref "LED63") (pin "4") (pinfunction "DO_4") (pintype "input"))
      (node (ref "LED66") (pin "2") (pinfunction "DI_2") (pintype "input"))
    )
    (net (code "53") (name "Net-(LED64-DI)") (class "Default")
      (node (ref "LED64") (pin "2") (pinfunction "DI_2") (pintype "input"))
      (node (ref "LED65") (pin "4") (pinfunction "DO_4") (pintype "input"))
    )
    (net (code "54") (name "Net-(LED64-DO)") (class "Default")
      (node (ref "LED64") (pin "4") (pinfunction "DO_4") (pintype "input"))
      (node (ref "LED69") (pin "2") (pinfunction "DI_2") (pintype "input"))
    )
    (net (code "55") (name "Net-(LED65-DI)") (class "Default")
      (node (ref "LED65") (pin "2") (pinfunction "DI_2") (pintype "input"))
      (node (ref "LED66") (pin "4") (pinfunction "DO_4") (pintype "input"))
    )
    (net (code "56") (name "Net-(LED67-DI)") (class "Default")
      (node (ref "LED67") (pin "2") (pinfunction "DI_2") (pintype "input"))
      (node (ref "LED68") (pin "4") (pinfunction "DO_4") (pintype "input"))
    )
    (net (code "57") (name "Net-(LED67-DO)") (class "Default")
      (node (ref "LED67") (pin "4") (pinfunction "DO_4") (pintype "input"))
      (node (ref "LED72") (pin "2") (pinfunction "DI_2") (pintype "input"))
    )
    (net (code "58") (name "Net-(LED68-DI)") (class "Default")
      (node (ref "LED68") (pin "2") (pinfunction "DI_2") (pintype "input"))
      (node (ref "LED69") (pin "4") (pinfunction "DO_4") (pintype "input"))
    )
    (net (code "59") (name "Net-(LED70-DI)") (class "Default")
      (node (ref "LED70") (pin "2") (pinfunction "DI_2") (pintype "input"))
      (node (ref "LED71") (pin "4") (pinfunction "DO_4") (pintype "input"))
    )
    (net (code "60") (name "Net-(LED70-DO)") (class "Default")
      (node (ref "LED70") (pin "4") (pinfunction "DO_4") (pintype "input"))
      (node (ref "LED75") (pin "2") (pinfunction "DI_2") (pintype "input"))
    )
    (net (code "61") (name "Net-(LED71-DI)") (class "Default")
      (node (ref "LED71") (pin "2") (pinfunction "DI_2") (pintype "input"))
      (node (ref "LED72") (pin "4") (pinfunction "DO_4") (pintype "input"))
    )
    (net (code "62") (name "Net-(LED73-DI)") (class "Default")
      (node (ref "LED73") (pin "2") (pinfunction "DI_2") (pintype "input"))
      (node (ref "LED74") (pin "4") (pinfunction "DO_4") (pintype "input"))
    )
    (net (code "63") (name "Net-(LED74-DI)") (class "Default")
      (node (ref "LED74") (pin "2") (pinfunction "DI_2") (pintype "input"))
      (node (ref "LED75") (pin "4") (pinfunction "DO_4") (pintype "input"))
    )
    (net (code "64") (name "Net-(LED76-DO)") (class "Default")
      (node (ref "LED76") (pin "4") (pinfunction "DO_4") (pintype "input"))
      (node (ref "LED77") (pin "2") (pinfunction "DI_2") (pintype "input"))
    )
    (net (code "65") (name "Net-(LED77-DO)") (class "Default")
      (node (ref "LED77") (pin "4") (pinfunction "DO_4") (pintype "input"))
      (node (ref "LED78") (pin "2") (pinfunction "DI_2") (pintype "input"))
    )
    (net (code "66") (name "Net-(LED78-DO)") (class "Default")
      (node (ref "LED78") (pin "4") (pinfunction "DO_4") (pintype "input"))
      (node (ref "LED79") (pin "2") (pinfunction "DI_2") (pintype "input"))
    )
    (net (code "67") (name "Net-(LED79-DO)") (class "Default")
      (node (ref "LED79") (pin "4") (pinfunction "DO_4") (pintype "input"))
      (node (ref "LED80") (pin "2") (pinfunction "DI_2") (pintype "input"))
    )
    (net (code "68") (name "OUT1") (class "Default")
      (node (ref "U1") (pin "7") (pinfunction "7_7") (pintype "input"))
      (node (ref "U2") (pin "2") (pinfunction "B_2") (pintype "input"))
    )
    (net (code "69") (name "OUT2") (class "Default")
      (node (ref "U1") (pin "5") (pinfunction "5_5") (pintype "input"))
      (node (ref "U3") (pin "2") (pinfunction "B_2") (pintype "input"))
    )
    (net (code "70") (name "OUT3") (class "Default")
      (node (ref "U1") (pin "3") (pinfunction "3_3") (pintype "input"))
    )
    (net (code "71") (name "OUT4") (class "Default")
      (node (ref "R1") (pin "2") (pinfunction "2_2") (pintype "input"))
      (node (ref "R40") (pin "1") (pinfunction "1_1") (pintype "input"))
      (node (ref "U1") (pin "4") (pinfunction "4_4") (pintype "input"))
    )
    (net (code "72") (name "OUT5") (class "Default")
      (node (ref "R41") (pin "1") (pinfunction "1_1") (pintype "input"))
      (node (ref "U1") (pin "6") (pinfunction "6_6") (pintype "input"))
      (node (ref "U4") (pin "1") (pinfunction "1_1") (pintype "input"))
    )
    (net (code "73") (name "OUT6") (class "Default")
      (node (ref "R42") (pin "1") (pinfunction "1_1") (pintype "input"))
      (node (ref "U1") (pin "8") (pinfunction "8_8") (pintype "input"))
      (node (ref "U4") (pin "2") (pinfunction "2_2") (pintype "input"))
    )
    (net (code "74") (name "SEP_OUT") (class "Default")
      (node (ref "LED46") (pin "2") (pinfunction "DI_2") (pintype "input"))
      (node (ref "LED80") (pin "4") (pinfunction "DO_4") (pintype "input"))
    )
    (net (code "75") (name "VCC3.3OUT") (class "Default")
      (node (ref "C17") (pin "2") (pinfunction "2_2") (pintype "input"))
      (node (ref "C20") (pin "1") (pinfunction "1_1") (pintype "input"))
      (node (ref "R41") (pin "2") (pinfunction "2_2") (pintype "input"))
      (node (ref "R42") (pin "2") (pinfunction "2_2") (pintype "input"))
      (node (ref "U1") (pin "10") (pinfunction "10_10") (pintype "input"))
    )
  )
)
